# 16x8_mono_LED_FeatherWing_rev_A.net
KiCad netlist of a schematic drawn in EAGLE
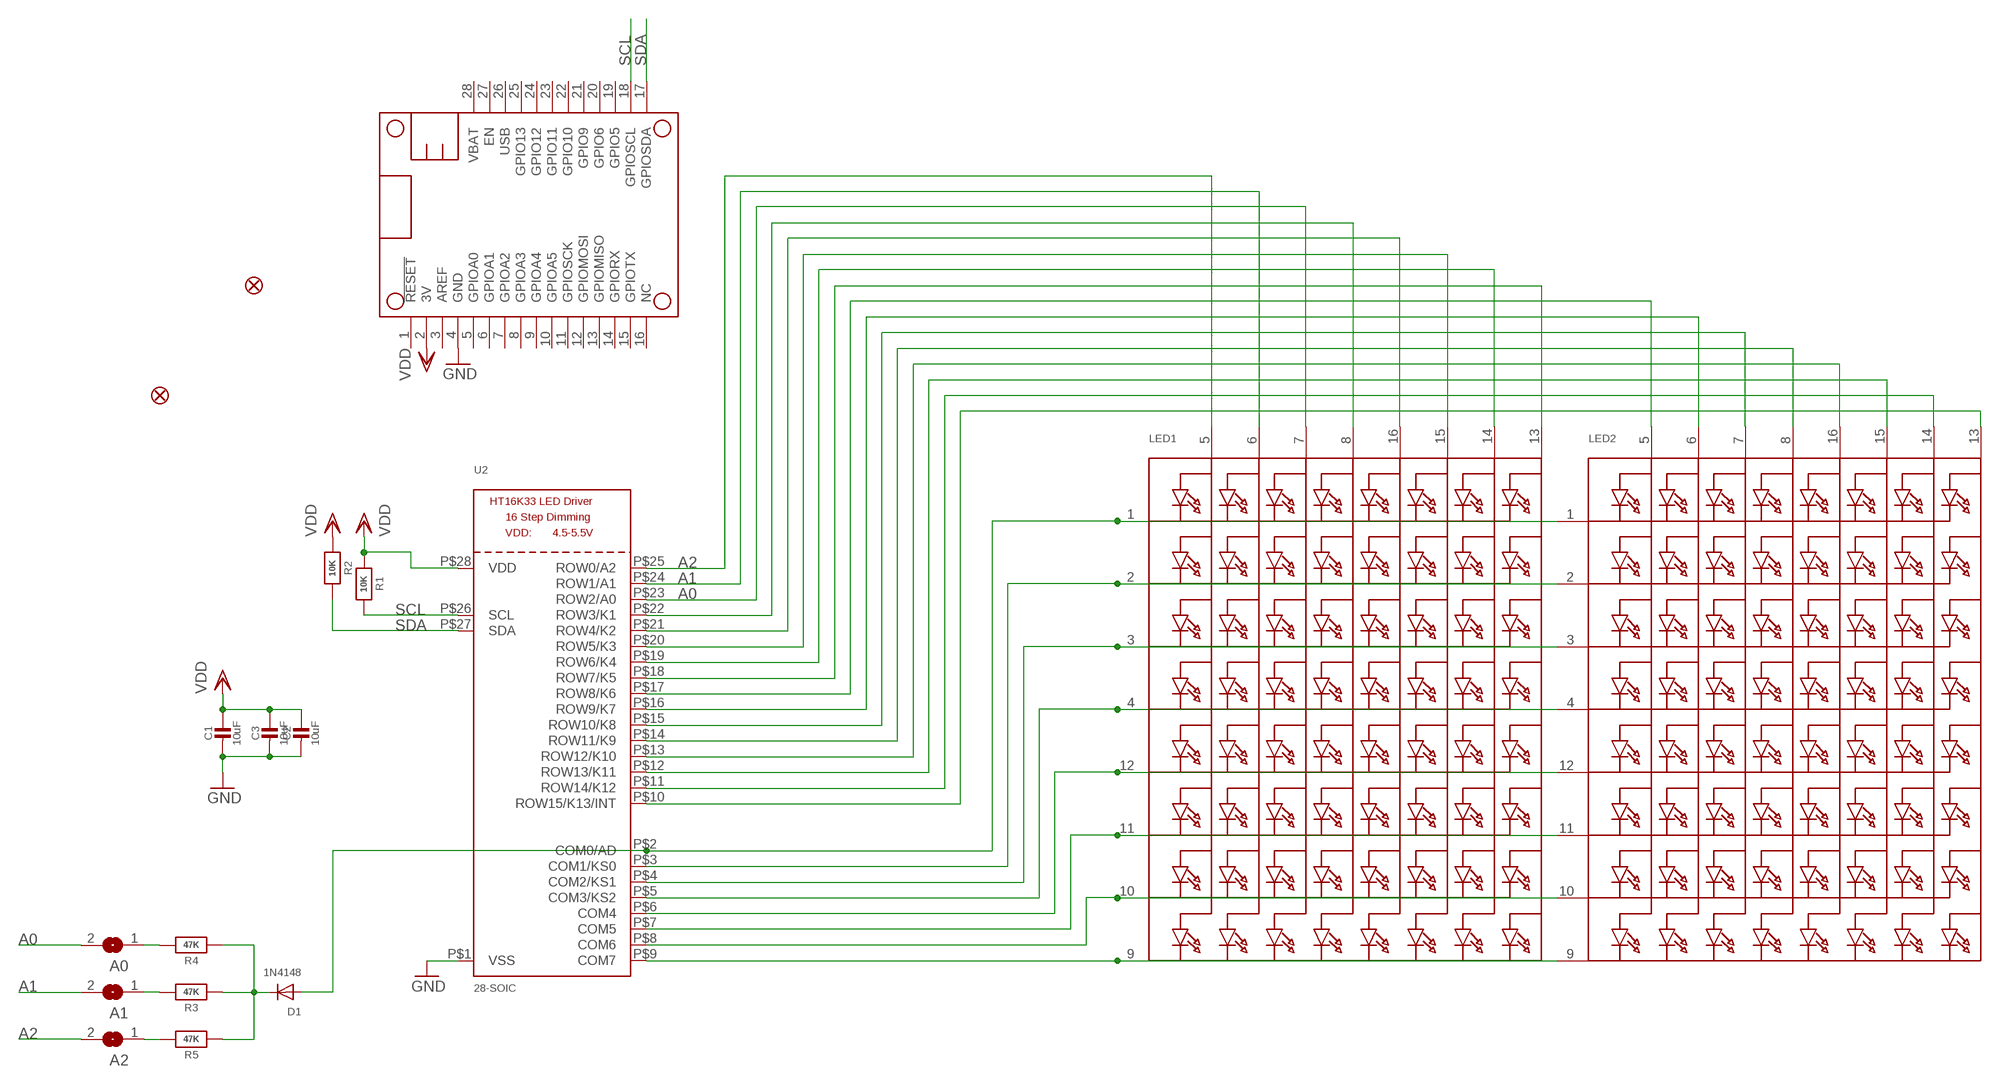
[diagram p0: schematic, sheet 1]

(export (version "E")
  (design (tool "Eeschema 10.0.6"))
  (components
    (comp (ref "A0")
      (value "SOLDERJUMPERREFLOW_NOPASTE")
      (footprint "eagle-import:SOLDERJUMPER_REFLOW_NOPASTE")
      (libsource (lib "eagle-import") (part "SOLDERJUMPERREFLOW_NOPASTE"))
    )
    (comp (ref "A1")
      (value "SOLDERJUMPERREFLOW_NOPASTE")
      (footprint "eagle-import:SOLDERJUMPER_REFLOW_NOPASTE")
      (libsource (lib "eagle-import") (part "SOLDERJUMPERREFLOW_NOPASTE"))
    )
    (comp (ref "A2")
      (value "SOLDERJUMPERREFLOW_NOPASTE")
      (footprint "eagle-import:SOLDERJUMPER_REFLOW_NOPASTE")
      (libsource (lib "eagle-import") (part "SOLDERJUMPERREFLOW_NOPASTE"))
    )
    (comp (ref "C1")
      (value "10uF")
      (footprint "eagle-import:0805-NO")
      (libsource (lib "eagle-import") (part "CAP_CERAMIC0805-NOOUTLINE"))
    )
    (comp (ref "C2")
      (value "10uF")
      (footprint "eagle-import:0805-NO")
      (libsource (lib "eagle-import") (part "CAP_CERAMIC0805-NOOUTLINE"))
    )
    (comp (ref "C3")
      (value "10uF")
      (footprint "eagle-import:0805-NO")
      (libsource (lib "eagle-import") (part "CAP_CERAMIC0805-NOOUTLINE"))
    )
    (comp (ref "D1")
      (value "1N4148")
      (footprint "eagle-import:SOD-323F")
      (libsource (lib "eagle-import") (part "DIODESOD-323F"))
    )
    (comp (ref "FID1")
      (value "FIDUCIAL\"\"")
      (footprint "eagle-import:FIDUCIAL_1MM")
      (libsource (lib "eagle-import") (part "FIDUCIAL{dblquote}{dblquote}"))
    )
    (comp (ref "FID2")
      (value "FIDUCIAL\"\"")
      (footprint "eagle-import:FIDUCIAL_1MM")
      (libsource (lib "eagle-import") (part "FIDUCIAL{dblquote}{dblquote}"))
    )
    (comp (ref "LED1")
      (value "DISP_SEGMENT_8X8_ROWCATHODE")
      (footprint "eagle-import:SEGMENT_BL-M07C881UR")
      (libsource (lib "eagle-import") (part "DISP_SEGMENT_8X8_ROWCATHODE"))
    )
    (comp (ref "LED2")
      (value "DISP_SEGMENT_8X8_ROWCATHODE")
      (footprint "eagle-import:SEGMENT_BL-M07C881UR")
      (libsource (lib "eagle-import") (part "DISP_SEGMENT_8X8_ROWCATHODE"))
    )
    (comp (ref "MS1")
      (value "FEATHERWING")
      (footprint "eagle-import:FEATHERWING")
      (libsource (lib "eagle-import") (part "FEATHERWING"))
    )
    (comp (ref "R1")
      (value "10K")
      (footprint "eagle-import:0805-NO")
      (libsource (lib "eagle-import") (part "RESISTOR0805_NOOUTLINE"))
    )
    (comp (ref "R2")
      (value "10K")
      (footprint "eagle-import:0805-NO")
      (libsource (lib "eagle-import") (part "RESISTOR0805_NOOUTLINE"))
    )
    (comp (ref "R3")
      (value "47K")
      (footprint "eagle-import:0805-NO")
      (libsource (lib "eagle-import") (part "RESISTOR0805_NOOUTLINE"))
    )
    (comp (ref "R4")
      (value "47K")
      (footprint "eagle-import:0805-NO")
      (libsource (lib "eagle-import") (part "RESISTOR0805_NOOUTLINE"))
    )
    (comp (ref "R5")
      (value "47K")
      (footprint "eagle-import:0805-NO")
      (libsource (lib "eagle-import") (part "RESISTOR0805_NOOUTLINE"))
    )
    (comp (ref "U2")
      (value "28-SOIC")
      (footprint "eagle-import:SOP28_300MIL_SKINNY")
      (libsource (lib "eagle-import") (part "HT16K33_SOP28_SKINNY"))
    )
  )
  (nets
    (net (code "1") (name "/A0") (class "Default")
      (node (ref "A0") (pin "2") (pinfunction "2_2") (pintype "passive"))
      (node (ref "LED1") (pin "7") (pinfunction "A3_7") (pintype "bidirectional"))
      (node (ref "U2") (pin "P$23") (pinfunction "ROW2/A0_P$23") (pintype "bidirectional"))
    )
    (net (code "2") (name "/A1") (class "Default")
      (node (ref "A1") (pin "2") (pinfunction "2_2") (pintype "passive"))
      (node (ref "LED1") (pin "6") (pinfunction "A2_6") (pintype "bidirectional"))
      (node (ref "U2") (pin "P$24") (pinfunction "ROW1/A1_P$24") (pintype "bidirectional"))
    )
    (net (code "3") (name "/A2") (class "Default")
      (node (ref "A2") (pin "2") (pinfunction "2_2") (pintype "passive"))
      (node (ref "LED1") (pin "5") (pinfunction "A1_5") (pintype "bidirectional"))
      (node (ref "U2") (pin "P$25") (pinfunction "ROW0/A2_P$25") (pintype "bidirectional"))
    )
    (net (code "4") (name "/SCL") (class "Default")
      (node (ref "MS1") (pin "18") (pinfunction "GPIOSCL_18") (pintype "bidirectional"))
      (node (ref "R1") (pin "2") (pinfunction "2_2") (pintype "passive"))
      (node (ref "U2") (pin "P$26") (pinfunction "SCL_P$26") (pintype "bidirectional"))
    )
    (net (code "5") (name "/SDA") (class "Default")
      (node (ref "MS1") (pin "17") (pinfunction "GPIOSDA_17") (pintype "bidirectional"))
      (node (ref "R2") (pin "2") (pinfunction "2_2") (pintype "passive"))
      (node (ref "U2") (pin "P$27") (pinfunction "SDA_P$27") (pintype "bidirectional"))
    )
    (net (code "6") (name "/USB") (class "Default")
      (node (ref "MS1") (pin "26") (pinfunction "USB_26") (pintype "power_in"))
    )
    (net (code "7") (name "/VBAT") (class "Default")
      (node (ref "MS1") (pin "28") (pinfunction "VBAT_28") (pintype "power_in"))
    )
    (net (code "8") (name "GND") (class "Default")
      (node (ref "C1") (pin "2") (pinfunction "2_2") (pintype "passive"))
      (node (ref "C2") (pin "2") (pinfunction "2_2") (pintype "passive"))
      (node (ref "C3") (pin "2") (pinfunction "2_2") (pintype "passive"))
      (node (ref "MS1") (pin "4") (pinfunction "GND_4") (pintype "power_in"))
      (node (ref "U2") (pin "P$1") (pinfunction "VSS_P$1") (pintype "bidirectional"))
    )
    (net (code "9") (name "Net-(A0-Pad1)") (class "Default")
      (node (ref "A0") (pin "1") (pinfunction "1_1") (pintype "passive"))
      (node (ref "R4") (pin "2") (pinfunction "2_2") (pintype "passive"))
    )
    (net (code "10") (name "Net-(A1-Pad1)") (class "Default")
      (node (ref "A1") (pin "1") (pinfunction "1_1") (pintype "passive"))
      (node (ref "R3") (pin "2") (pinfunction "2_2") (pintype "passive"))
    )
    (net (code "11") (name "Net-(A2-Pad1)") (class "Default")
      (node (ref "A2") (pin "1") (pinfunction "1_1") (pintype "passive"))
      (node (ref "R5") (pin "2") (pinfunction "2_2") (pintype "passive"))
    )
    (net (code "12") (name "Net-(D1-PadC)") (class "Default")
      (node (ref "D1") (pin "C") (pinfunction "C_C") (pintype "passive"))
      (node (ref "R3") (pin "1") (pinfunction "1_1") (pintype "passive"))
      (node (ref "R4") (pin "1") (pinfunction "1_1") (pintype "passive"))
      (node (ref "R5") (pin "1") (pinfunction "1_1") (pintype "passive"))
    )
    (net (code "13") (name "Net-(LED1-A4)") (class "Default")
      (node (ref "LED1") (pin "8") (pinfunction "A4_8") (pintype "bidirectional"))
      (node (ref "U2") (pin "P$22") (pinfunction "ROW3/K1_P$22") (pintype "bidirectional"))
    )
    (net (code "14") (name "Net-(LED1-A5)") (class "Default")
      (node (ref "LED1") (pin "16") (pinfunction "A5_16") (pintype "bidirectional"))
      (node (ref "U2") (pin "P$21") (pinfunction "ROW4/K2_P$21") (pintype "bidirectional"))
    )
    (net (code "15") (name "Net-(LED1-A6)") (class "Default")
      (node (ref "LED1") (pin "15") (pinfunction "A6_15") (pintype "bidirectional"))
      (node (ref "U2") (pin "P$20") (pinfunction "ROW5/K3_P$20") (pintype "bidirectional"))
    )
    (net (code "16") (name "Net-(LED1-A7)") (class "Default")
      (node (ref "LED1") (pin "14") (pinfunction "A7_14") (pintype "bidirectional"))
      (node (ref "U2") (pin "P$19") (pinfunction "ROW6/K4_P$19") (pintype "bidirectional"))
    )
    (net (code "17") (name "Net-(LED1-A8)") (class "Default")
      (node (ref "LED1") (pin "13") (pinfunction "A8_13") (pintype "bidirectional"))
      (node (ref "U2") (pin "P$18") (pinfunction "ROW7/K5_P$18") (pintype "bidirectional"))
    )
    (net (code "18") (name "Net-(LED1-K1)") (class "Default")
      (node (ref "D1") (pin "A") (pinfunction "A_A") (pintype "passive"))
      (node (ref "LED1") (pin "1") (pinfunction "K1_1") (pintype "bidirectional"))
      (node (ref "LED2") (pin "1") (pinfunction "K1_1") (pintype "bidirectional"))
      (node (ref "U2") (pin "P$2") (pinfunction "COM0/AD_P$2") (pintype "bidirectional"))
    )
    (net (code "19") (name "Net-(LED1-K2)") (class "Default")
      (node (ref "LED1") (pin "2") (pinfunction "K2_2") (pintype "bidirectional"))
      (node (ref "LED2") (pin "2") (pinfunction "K2_2") (pintype "bidirectional"))
      (node (ref "U2") (pin "P$3") (pinfunction "COM1/KS0_P$3") (pintype "bidirectional"))
    )
    (net (code "20") (name "Net-(LED1-K3)") (class "Default")
      (node (ref "LED1") (pin "3") (pinfunction "K3_3") (pintype "bidirectional"))
      (node (ref "LED2") (pin "3") (pinfunction "K3_3") (pintype "bidirectional"))
      (node (ref "U2") (pin "P$4") (pinfunction "COM2/KS1_P$4") (pintype "bidirectional"))
    )
    (net (code "21") (name "Net-(LED1-K4)") (class "Default")
      (node (ref "LED1") (pin "4") (pinfunction "K4_4") (pintype "bidirectional"))
      (node (ref "LED2") (pin "4") (pinfunction "K4_4") (pintype "bidirectional"))
      (node (ref "U2") (pin "P$5") (pinfunction "COM3/KS2_P$5") (pintype "bidirectional"))
    )
    (net (code "22") (name "Net-(LED1-K5)") (class "Default")
      (node (ref "LED1") (pin "12") (pinfunction "K5_12") (pintype "bidirectional"))
      (node (ref "LED2") (pin "12") (pinfunction "K5_12") (pintype "bidirectional"))
      (node (ref "U2") (pin "P$6") (pinfunction "COM4_P$6") (pintype "bidirectional"))
    )
    (net (code "23") (name "Net-(LED1-K6)") (class "Default")
      (node (ref "LED1") (pin "11") (pinfunction "K6_11") (pintype "bidirectional"))
      (node (ref "LED2") (pin "11") (pinfunction "K6_11") (pintype "bidirectional"))
      (node (ref "U2") (pin "P$7") (pinfunction "COM5_P$7") (pintype "bidirectional"))
    )
    (net (code "24") (name "Net-(LED1-K7)") (class "Default")
      (node (ref "LED1") (pin "10") (pinfunction "K7_10") (pintype "bidirectional"))
      (node (ref "LED2") (pin "10") (pinfunction "K7_10") (pintype "bidirectional"))
      (node (ref "U2") (pin "P$8") (pinfunction "COM6_P$8") (pintype "bidirectional"))
    )
    (net (code "25") (name "Net-(LED1-K8)") (class "Default")
      (node (ref "LED1") (pin "9") (pinfunction "K8_9") (pintype "bidirectional"))
      (node (ref "LED2") (pin "9") (pinfunction "K8_9") (pintype "bidirectional"))
      (node (ref "U2") (pin "P$9") (pinfunction "COM7_P$9") (pintype "bidirectional"))
    )
    (net (code "26") (name "Net-(LED2-A1)") (class "Default")
      (node (ref "LED2") (pin "5") (pinfunction "A1_5") (pintype "bidirectional"))
      (node (ref "U2") (pin "P$17") (pinfunction "ROW8/K6_P$17") (pintype "bidirectional"))
    )
    (net (code "27") (name "Net-(LED2-A2)") (class "Default")
      (node (ref "LED2") (pin "6") (pinfunction "A2_6") (pintype "bidirectional"))
      (node (ref "U2") (pin "P$16") (pinfunction "ROW9/K7_P$16") (pintype "bidirectional"))
    )
    (net (code "28") (name "Net-(LED2-A3)") (class "Default")
      (node (ref "LED2") (pin "7") (pinfunction "A3_7") (pintype "bidirectional"))
      (node (ref "U2") (pin "P$15") (pinfunction "ROW10/K8_P$15") (pintype "bidirectional"))
    )
    (net (code "29") (name "Net-(LED2-A4)") (class "Default")
      (node (ref "LED2") (pin "8") (pinfunction "A4_8") (pintype "bidirectional"))
      (node (ref "U2") (pin "P$14") (pinfunction "ROW11/K9_P$14") (pintype "bidirectional"))
    )
    (net (code "30") (name "Net-(LED2-A5)") (class "Default")
      (node (ref "LED2") (pin "16") (pinfunction "A5_16") (pintype "bidirectional"))
      (node (ref "U2") (pin "P$13") (pinfunction "ROW12/K10_P$13") (pintype "bidirectional"))
    )
    (net (code "31") (name "Net-(LED2-A6)") (class "Default")
      (node (ref "LED2") (pin "15") (pinfunction "A6_15") (pintype "bidirectional"))
      (node (ref "U2") (pin "P$12") (pinfunction "ROW13/K11_P$12") (pintype "bidirectional"))
    )
    (net (code "32") (name "Net-(LED2-A7)") (class "Default")
      (node (ref "LED2") (pin "14") (pinfunction "A7_14") (pintype "bidirectional"))
      (node (ref "U2") (pin "P$11") (pinfunction "ROW14/K12_P$11") (pintype "bidirectional"))
    )
    (net (code "33") (name "Net-(LED2-A8)") (class "Default")
      (node (ref "LED2") (pin "13") (pinfunction "A8_13") (pintype "bidirectional"))
      (node (ref "U2") (pin "P$10") (pinfunction "ROW15/K13/INT_P$10") (pintype "bidirectional"))
    )
    (net (code "34") (name "VDD") (class "Default")
      (node (ref "C1") (pin "1") (pinfunction "1_1") (pintype "passive"))
      (node (ref "C2") (pin "1") (pinfunction "1_1") (pintype "passive"))
      (node (ref "C3") (pin "1") (pinfunction "1_1") (pintype "passive"))
      (node (ref "MS1") (pin "2") (pinfunction "3V_2") (pintype "power_in"))
      (node (ref "R1") (pin "1") (pinfunction "1_1") (pintype "passive"))
      (node (ref "R2") (pin "1") (pinfunction "1_1") (pintype "passive"))
      (node (ref "U2") (pin "P$28") (pinfunction "VDD_P$28") (pintype "bidirectional"))
    )
    (net (code "35") (name "unconnected-(MS1-AREF-Pad3)") (class "Default")
      (node (ref "MS1") (pin "3") (pinfunction "AREF_3") (pintype "passive"))
    )
    (net (code "36") (name "unconnected-(MS1-EN-Pad27)") (class "Default")
      (node (ref "MS1") (pin "27") (pinfunction "EN_27") (pintype "passive"))
    )
    (net (code "37") (name "unconnected-(MS1-GPIO5-Pad19)") (class "Default")
      (node (ref "MS1") (pin "19") (pinfunction "GPIO5_19") (pintype "bidirectional"))
    )
    (net (code "38") (name "unconnected-(MS1-GPIO6-Pad20)") (class "Default")
      (node (ref "MS1") (pin "20") (pinfunction "GPIO6_20") (pintype "bidirectional"))
    )
    (net (code "39") (name "unconnected-(MS1-GPIO9-Pad21)") (class "Default")
      (node (ref "MS1") (pin "21") (pinfunction "GPIO9_21") (pintype "bidirectional"))
    )
    (net (code "40") (name "unconnected-(MS1-GPIO10-Pad22)") (class "Default")
      (node (ref "MS1") (pin "22") (pinfunction "GPIO10_22") (pintype "bidirectional"))
    )
    (net (code "41") (name "unconnected-(MS1-GPIO11-Pad23)") (class "Default")
      (node (ref "MS1") (pin "23") (pinfunction "GPIO11_23") (pintype "bidirectional"))
    )
    (net (code "42") (name "unconnected-(MS1-GPIO12-Pad24)") (class "Default")
      (node (ref "MS1") (pin "24") (pinfunction "GPIO12_24") (pintype "bidirectional"))
    )
    (net (code "43") (name "unconnected-(MS1-GPIO13-Pad25)") (class "Default")
      (node (ref "MS1") (pin "25") (pinfunction "GPIO13_25") (pintype "bidirectional"))
    )
    (net (code "44") (name "unconnected-(MS1-GPIOA0-Pad5)") (class "Default")
      (node (ref "MS1") (pin "5") (pinfunction "GPIOA0_5") (pintype "bidirectional"))
    )
    (net (code "45") (name "unconnected-(MS1-GPIOA1-Pad6)") (class "Default")
      (node (ref "MS1") (pin "6") (pinfunction "GPIOA1_6") (pintype "bidirectional"))
    )
    (net (code "46") (name "unconnected-(MS1-GPIOA2-Pad7)") (class "Default")
      (node (ref "MS1") (pin "7") (pinfunction "GPIOA2_7") (pintype "bidirectional"))
    )
    (net (code "47") (name "unconnected-(MS1-GPIOA3-Pad8)") (class "Default")
      (node (ref "MS1") (pin "8") (pinfunction "GPIOA3_8") (pintype "bidirectional"))
    )
    (net (code "48") (name "unconnected-(MS1-GPIOA4-Pad9)") (class "Default")
      (node (ref "MS1") (pin "9") (pinfunction "GPIOA4_9") (pintype "bidirectional"))
    )
    (net (code "49") (name "unconnected-(MS1-GPIOA5-Pad10)") (class "Default")
      (node (ref "MS1") (pin "10") (pinfunction "GPIOA5_10") (pintype "bidirectional"))
    )
    (net (code "50") (name "unconnected-(MS1-GPIOMISO-Pad13)") (class "Default")
      (node (ref "MS1") (pin "13") (pinfunction "GPIOMISO_13") (pintype "bidirectional"))
    )
    (net (code "51") (name "unconnected-(MS1-GPIOMOSI-Pad12)") (class "Default")
      (node (ref "MS1") (pin "12") (pinfunction "GPIOMOSI_12") (pintype "bidirectional"))
    )
    (net (code "52") (name "unconnected-(MS1-GPIORX-Pad14)") (class "Default")
      (node (ref "MS1") (pin "14") (pinfunction "GPIORX_14") (pintype "bidirectional"))
    )
    (net (code "53") (name "unconnected-(MS1-GPIOSCK-Pad11)") (class "Default")
      (node (ref "MS1") (pin "11") (pinfunction "GPIOSCK_11") (pintype "bidirectional"))
    )
    (net (code "54") (name "unconnected-(MS1-GPIOTX-Pad15)") (class "Default")
      (node (ref "MS1") (pin "15") (pinfunction "GPIOTX_15") (pintype "bidirectional"))
    )
    (net (code "55") (name "unconnected-(MS1-NC-Pad16)") (class "Default")
      (node (ref "MS1") (pin "16") (pinfunction "NC_16") (pintype "passive"))
    )
    (net (code "56") (name "unconnected-(MS1-~{RESET}-Pad1)") (class "Default")
      (node (ref "MS1") (pin "1") (pinfunction "~{RESET}_1") (pintype "input"))
    )
  )
)
